# smartBattery.net
KiCad netlist of a schematic drawn in Altium Designer
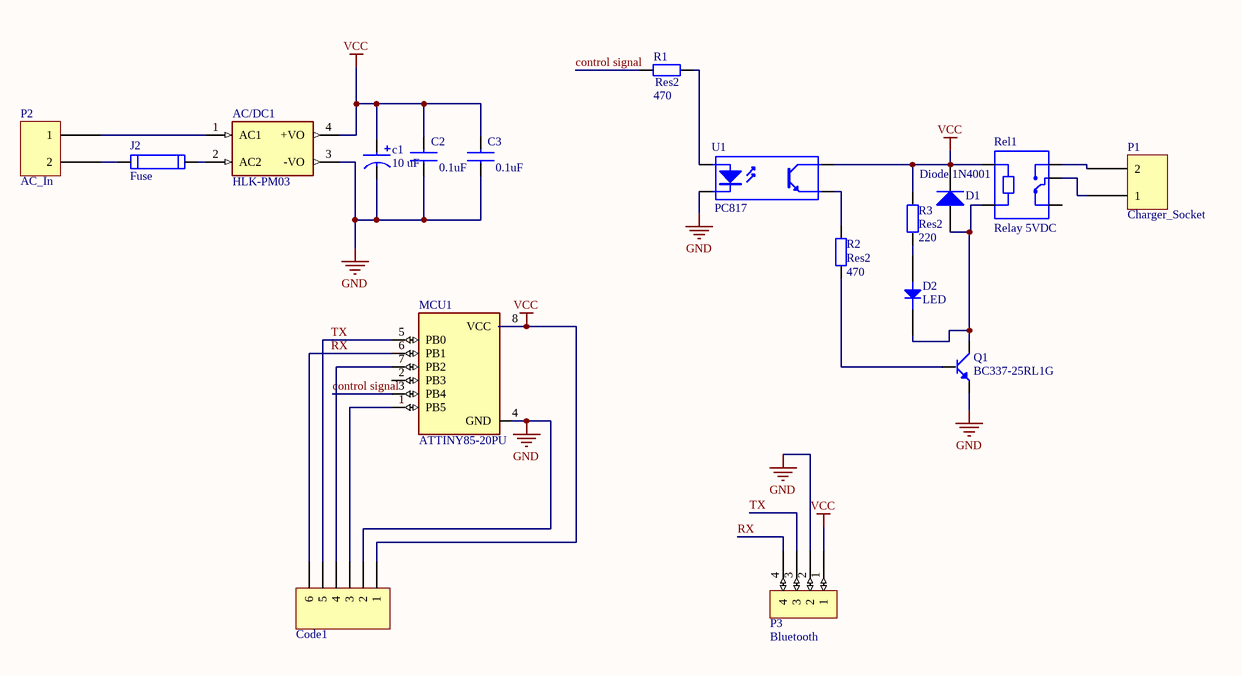
[diagram p0: smartBattery.SchDoc]

(export (version "E")
  (design (tool "Eeschema 10.0.6"))
  (components
    (comp (ref "AC/DC1")
      (value "HLK-PM03")
      (footprint "CONV_HLK-PM03")
      (description "AC DC 3W power module")
      (fields (field (name "MF") "Hi-link"))
      (libsource (lib "HLK-PM03") (part "HLK-PM03"))
    )
    (comp (ref "c1")
      (value "10 uF")
      (footprint "AluminumCap")
      (description "Cap Aluminum 10uF 400V 20% (10 X 16mm) Radial 5mm 150mA 8000 hr 105C Bulk")
      (libsource (lib "AhmedOsama") (part "AluminumCap"))
    )
    (comp (ref "C2")
      (value "0.1uF")
      (footprint "ceramicCapTHT")
      (description "22pF 50 V dc Ceramic Single Layer Capacitor; Y5R Dielectric THT F Series")
      (libsource (lib "AhmedOsama") (part "ceramicCapTHT"))
    )
    (comp (ref "C3")
      (value "0.1uF")
      (footprint "ceramicCapTHT")
      (description "22pF 50 V dc Ceramic Single Layer Capacitor; Y5R Dielectric THT F Series")
      (libsource (lib "AhmedOsama") (part "ceramicCapTHT"))
    )
    (comp (ref "Code1")
      (value "~")
      (footprint "HDR1X6")
      (description "Header, 6-Pin")
      (fields (field (name "PUBLISHER") "Altium Limited"))
      (libsource (lib "Miscellaneous Connectors") (part "Header 6"))
    )
    (comp (ref "D1")
      (value "Diode 1N4001")
      (footprint "DO-41")
      (description "1 Amp General Purpose Rectifier")
      (fields (field (name "PUBLISHER") "Altium Limited"))
      (libsource (lib "Miscellaneous Devices") (part "Diode 1N4001"))
    )
    (comp (ref "D2")
      (value "LED")
      (footprint "SDO27")
      (description "NTE ELECTRONICS - 1N4148 - Small Signal Diode, Switching, Single, 75 V, 300 mA, 1 V, 4 ns, 1 A")
      (libsource (lib "AhmedOsama") (part "1N4148"))
    )
    (comp (ref "J2")
      (value "Fuse")
      (footprint "696310001002")
      (description "Fuse Holder 20A 250V 1 Circuit Cartridge Through Hole")
      (fields (field (name "MP") "696310001002") (field (name "MF") "Wurth Electronics"))
      (libsource (lib "696310001002") (part "696310001002"))
    )
    (comp (ref "MCU1")
      (value "ATTINY85-20PU")
      (footprint "DIP762W46P254L927H533Q8B")
      (fields (field (name "MF") "Microchip"))
      (libsource (lib "ATTINY85-20PU") (part "ATTINY85-20PU"))
    )
    (comp (ref "P1")
      (value "Charger_Socket")
      (footprint "TB_2Pin")
      (description "TERM BLK 2P SIDE ENT 2.54MM PCB")
      (fields (field (name "VOLTAGE") "125V"))
      (libsource (lib "AhmedOsama") (part "OSTVN02A150"))
    )
    (comp (ref "P2")
      (value "AC_In")
      (footprint "TB_2Pin")
      (description "TERM BLK 2P SIDE ENT 2.54MM PCB")
      (fields (field (name "VOLTAGE") "125V"))
      (libsource (lib "") (part "OSTVN02A150_1"))
    )
    (comp (ref "P3")
      (value "Bluetooth")
      (footprint "pinhead_01x04")
      (description "pin header 01x04 straight")
      (libsource (lib "AhmedOsama") (part "pinheadF_01x04"))
    )
    (comp (ref "Q1")
      (value "BC337-25RL1G")
      (footprint "TO-92")
      (description "Trans Gp Bjt NPN 45V 0.8A 625MW 3-PIN TO-92 T/r")
      (libsource (lib "AhmedOsama") (part "BC337-25RL1G"))
    )
    (comp (ref "R1")
      (value "Res2")
      (footprint "AXIAL-0.4")
      (description "Resistor")
      (fields (field (name "ALTIUM_VALUE") "470") (field (name "PUBLISHER") "Altium Limited"))
      (libsource (lib "") (part "Res2_1"))
    )
    (comp (ref "R2")
      (value "Res2")
      (footprint "AXIAL-0.4")
      (description "Resistor")
      (fields (field (name "ALTIUM_VALUE") "470") (field (name "PUBLISHER") "Altium Limited"))
      (libsource (lib "Miscellaneous Devices") (part "Res2"))
    )
    (comp (ref "R3")
      (value "Res2")
      (footprint "AXIAL-0.4")
      (description "Resistor")
      (fields (field (name "ALTIUM_VALUE") "220") (field (name "PUBLISHER") "Altium Limited"))
      (libsource (lib "Miscellaneous Devices") (part "Res2"))
    )
    (comp (ref "Rel1")
      (value "Relay 5VDC")
      (footprint "RELAY_SRD-05VDC-SL-C")
      (fields (field (name "MP") "SRD-05VDC-SL-C") (field (name "MF") "Songle Relay"))
      (libsource (lib "SRD-05VDC-SL-C") (part "SRD-05VDC-SL-C"))
    )
    (comp (ref "U1")
      (value "PC817")
      (footprint "DIP-4")
      (description "4-Pin Phototransistor Optocoupler")
      (fields (field (name "PUBLISHER") "Altium Limited"))
      (libsource (lib "Miscellaneous Devices") (part "Optoisolator1"))
    )
  )
  (nets
    (net (code "1") (name "/RX") (class "Default")
      (node (ref "Code1") (pin "6") (pinfunction "6_6") (pintype "passive"))
      (node (ref "MCU1") (pin "6") (pinfunction "PB1_6") (pintype "bidirectional"))
      (node (ref "P3") (pin "4") (pinfunction "4_4") (pintype "bidirectional"))
    )
    (net (code "2") (name "/TX") (class "Default")
      (node (ref "Code1") (pin "5") (pinfunction "5_5") (pintype "passive"))
      (node (ref "MCU1") (pin "5") (pinfunction "PB0_5") (pintype "bidirectional"))
      (node (ref "P3") (pin "3") (pinfunction "3_3") (pintype "bidirectional"))
    )
    (net (code "3") (name "/control signal") (class "Default")
      (node (ref "MCU1") (pin "3") (pinfunction "PB4_3") (pintype "bidirectional"))
      (node (ref "R1") (pin "1") (pinfunction "1_1") (pintype "passive"))
    )
    (net (code "4") (name "GND") (class "Default")
      (node (ref "AC/DC1") (pin "3") (pinfunction "-VO_3") (pintype "output"))
      (node (ref "C2") (pin "1") (pinfunction "1_1") (pintype "passive"))
      (node (ref "C3") (pin "1") (pinfunction "1_1") (pintype "passive"))
      (node (ref "Code1") (pin "2") (pinfunction "2_2") (pintype "passive"))
      (node (ref "MCU1") (pin "4") (pinfunction "GND_4") (pintype "power_in"))
      (node (ref "P3") (pin "2") (pinfunction "2_2") (pintype "bidirectional"))
      (node (ref "Q1") (pin "3") (pinfunction "E_3") (pintype "power_in"))
      (node (ref "U1") (pin "2") (pinfunction "K_2") (pintype "passive"))
      (node (ref "c1") (pin "2") (pinfunction "2_2") (pintype "passive"))
    )
    (net (code "5") (name "Net-(AC/DC1-AC1)") (class "Default")
      (node (ref "AC/DC1") (pin "1") (pinfunction "AC1_1") (pintype "input"))
      (node (ref "P2") (pin "1") (pinfunction "1_1") (pintype "power_in"))
    )
    (net (code "6") (name "Net-(AC/DC1-AC2)") (class "Default")
      (node (ref "AC/DC1") (pin "2") (pinfunction "AC2_2") (pintype "input"))
      (node (ref "J2") (pin "2") (pinfunction "2_2") (pintype "passive"))
    )
    (net (code "7") (name "Net-(D1-A)") (class "Default")
      (node (ref "D1") (pin "1") (pinfunction "A_1") (pintype "passive"))
      (node (ref "D2") (pin "2") (pinfunction "2_2") (pintype "power_in"))
      (node (ref "Q1") (pin "1") (pinfunction "C_1") (pintype "power_in"))
      (node (ref "Rel1") (pin "A2") (pinfunction "A2_A2") (pintype "passive"))
    )
    (net (code "8") (name "Net-(D2-Pad1)") (class "Default")
      (node (ref "D2") (pin "1") (pinfunction "1_1") (pintype "power_in"))
      (node (ref "R3") (pin "1") (pinfunction "1_1") (pintype "passive"))
    )
    (net (code "9") (name "Net-(J2-Pad1)") (class "Default")
      (node (ref "J2") (pin "1") (pinfunction "1_1") (pintype "passive"))
      (node (ref "P2") (pin "2") (pinfunction "2_2") (pintype "power_in"))
    )
    (net (code "10") (name "Net-(MCU1-PB2)") (class "Default")
      (node (ref "Code1") (pin "4") (pinfunction "4_4") (pintype "passive"))
      (node (ref "MCU1") (pin "7") (pinfunction "PB2_7") (pintype "bidirectional"))
    )
    (net (code "11") (name "Net-(MCU1-PB5)") (class "Default")
      (node (ref "Code1") (pin "3") (pinfunction "3_3") (pintype "passive"))
      (node (ref "MCU1") (pin "1") (pinfunction "PB5_1") (pintype "bidirectional"))
    )
    (net (code "12") (name "Net-(P1-Pad1)") (class "Default")
      (node (ref "P1") (pin "1") (pinfunction "1_1") (pintype "power_in"))
      (node (ref "Rel1") (pin "COM") (pinfunction "COM_COM") (pintype "passive"))
    )
    (net (code "13") (name "Net-(P1-Pad2)") (class "Default")
      (node (ref "P1") (pin "2") (pinfunction "2_2") (pintype "power_in"))
      (node (ref "Rel1") (pin "NO") (pinfunction "NO_NO") (pintype "passive"))
    )
    (net (code "14") (name "Net-(Q1-B)") (class "Default")
      (node (ref "Q1") (pin "2") (pinfunction "B_2") (pintype "power_in"))
      (node (ref "R2") (pin "1") (pinfunction "1_1") (pintype "passive"))
    )
    (net (code "15") (name "Net-(U1-A)") (class "Default")
      (node (ref "R1") (pin "2") (pinfunction "2_2") (pintype "passive"))
      (node (ref "U1") (pin "1") (pinfunction "A_1") (pintype "passive"))
    )
    (net (code "16") (name "Net-(U1-E)") (class "Default")
      (node (ref "R2") (pin "2") (pinfunction "2_2") (pintype "passive"))
      (node (ref "U1") (pin "3") (pinfunction "E_3") (pintype "passive"))
    )
    (net (code "17") (name "VCC") (class "Default")
      (node (ref "AC/DC1") (pin "4") (pinfunction "+VO_4") (pintype "output"))
      (node (ref "C2") (pin "2") (pinfunction "2_2") (pintype "passive"))
      (node (ref "C3") (pin "2") (pinfunction "2_2") (pintype "passive"))
      (node (ref "Code1") (pin "1") (pinfunction "1_1") (pintype "passive"))
      (node (ref "D1") (pin "2") (pinfunction "K_2") (pintype "passive"))
      (node (ref "MCU1") (pin "8") (pinfunction "VCC_8") (pintype "power_in"))
      (node (ref "P3") (pin "1") (pinfunction "1_1") (pintype "bidirectional"))
      (node (ref "R3") (pin "2") (pinfunction "2_2") (pintype "passive"))
      (node (ref "Rel1") (pin "A1") (pinfunction "A1_A1") (pintype "passive"))
      (node (ref "U1") (pin "4") (pinfunction "C_4") (pintype "passive"))
      (node (ref "c1") (pin "1") (pinfunction "1_1") (pintype "passive"))
    )
    (net (code "18") (name "unconnected-(MCU1-PB3-Pad2)") (class "Default")
      (node (ref "MCU1") (pin "2") (pinfunction "PB3_2") (pintype "bidirectional"))
    )
    (net (code "19") (name "unconnected-(Rel1-PadNC)") (class "Default")
      (node (ref "Rel1") (pin "NC") (pinfunction "NC_NC") (pintype "passive"))
    )
  )
)
